# design.net
KiCad netlist of a schematic drawn in Altium Designer
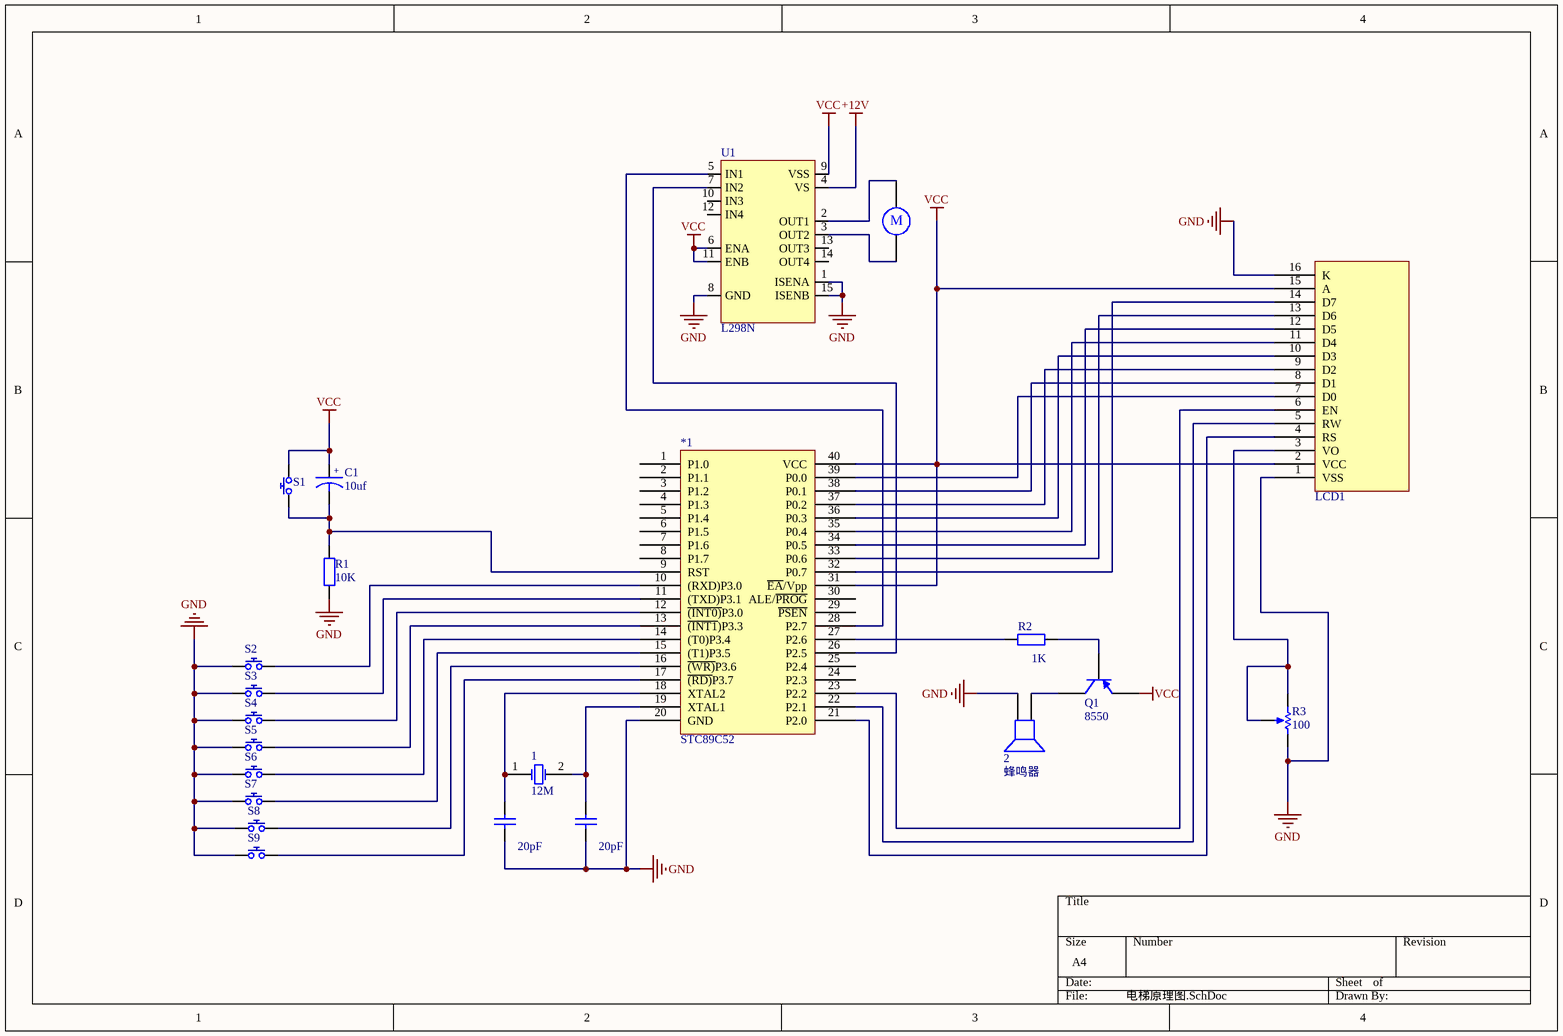
[diagram p0: 电梯原理图.SchDoc]

(export (version "E")
  (design (tool "Eeschema 10.0.6"))
  (components
    (comp (ref "*1") (value "STC89C52") (libsource (lib "AT89C52") (part "Component_1")))
    (comp (ref "1")
      (value "12M")
      (footprint "BCY-W2/D3.1")
      (description "Crystal Oscillator")
      (fields (field (name "PUBLISHER") "Altium Limited"))
      (libsource (lib "Miscellaneous Devices") (part "XTAL"))
    )
    (comp (ref "2")
      (value "蜂鸣器")
      (footprint "PIN2")
      (description "Loudspeaker")
      (fields (field (name "PUBLISHER") "Altium Limited"))
      (libsource (lib "Miscellaneous Devices") (part "Speaker"))
    )
    (comp (ref "B1")
      (value "Motor")
      (footprint "RB5-10.5")
      (description "Motor, General Kind")
      (fields (field (name "PUBLISHER") "Altium Limited"))
      (libsource (lib "Miscellaneous Devices") (part "Motor"))
    )
    (comp (ref "C1")
      (value "10uf")
      (footprint "RB.3/.6")
      (description "电解电容")
      (libsource (lib "MINE") (part "CAP-T"))
    )
    (comp (ref "C2")
      (value "20pF")
      (footprint "RAD-0.3")
      (description "Capacitor")
      (fields (field (name "Comment") "Cap") (field (name "PUBLISHER") "Altium Limited"))
      (libsource (lib "Miscellaneous Devices") (part "Cap"))
    )
    (comp (ref "C3")
      (value "20pF")
      (footprint "RAD-0.3")
      (description "Capacitor")
      (fields (field (name "Comment") "Cap") (field (name "PUBLISHER") "Altium Limited"))
      (libsource (lib "Miscellaneous Devices") (part "Cap"))
    )
    (comp (ref "LCD1") (value "Component_1") (libsource (lib "LCD1602") (part "Component_1")))
    (comp (ref "Q1")
      (value "8550")
      (footprint "SOT-23B_N")
      (description "PNP Bipolar Transistor")
      (fields (field (name "PUBLISHER") "Altium Limited"))
      (libsource (lib "Miscellaneous Devices") (part "PNP"))
    )
    (comp (ref "R1")
      (value "10K")
      (footprint "R-AXIAL0.4")
      (description "插件电阻")
      (libsource (lib "MINE") (part "RES"))
    )
    (comp (ref "R2")
      (value "1K")
      (footprint "AXIAL-0.4")
      (description "Resistor")
      (fields (field (name "Comment") "Res2") (field (name "PUBLISHER") "Altium Limited"))
      (libsource (lib "Miscellaneous Devices") (part "Res2"))
    )
    (comp (ref "R3")
      (value "100")
      (footprint "VR5")
      (description "Potentiometer")
      (fields (field (name "Comment") "RPot") (field (name "PUBLISHER") "Altium Limited"))
      (libsource (lib "Miscellaneous Devices") (part "RPot"))
    )
    (comp (ref "S1")
      (value "~")
      (footprint "KEY_4PIN")
      (description "按键开关")
      (libsource (lib "MINE") (part "Key"))
    )
    (comp (ref "S2")
      (value "~")
      (footprint "KEY_4PIN")
      (description "按键开关")
      (libsource (lib "MINE") (part "Key"))
    )
    (comp (ref "S3")
      (value "~")
      (footprint "KEY_4PIN")
      (description "按键开关")
      (libsource (lib "MINE") (part "Key"))
    )
    (comp (ref "S4")
      (value "~")
      (footprint "KEY_4PIN")
      (description "按键开关")
      (libsource (lib "MINE") (part "Key"))
    )
    (comp (ref "S5")
      (value "~")
      (footprint "KEY_4PIN")
      (description "按键开关")
      (libsource (lib "MINE") (part "Key"))
    )
    (comp (ref "S6")
      (value "~")
      (footprint "KEY_4PIN")
      (description "按键开关")
      (libsource (lib "MINE") (part "Key"))
    )
    (comp (ref "S7")
      (value "~")
      (footprint "KEY_4PIN")
      (description "按键开关")
      (libsource (lib "MINE") (part "Key"))
    )
    (comp (ref "S8")
      (value "~")
      (footprint "KEY_4PIN")
      (description "按键开关")
      (libsource (lib "MINE") (part "Key"))
    )
    (comp (ref "S9")
      (value "~")
      (footprint "KEY_4PIN")
      (description "按键开关")
      (libsource (lib "MINE") (part "Key"))
    )
    (comp (ref "U1") (value "L298N") (footprint "L298N") (libsource (lib "IC芯片") (part "L298N")))
  )
  (nets
    (net (code "1") (name "+12V") (class "Default")
      (node (ref "U1") (pin "4") (pinfunction "VS_4") (pintype "passive"))
    )
    (net (code "2") (name "GND") (class "Default")
      (node (ref "*1") (pin "20") (pinfunction "GND_20") (pintype "passive"))
      (node (ref "2") (pin "2") (pinfunction "2_2") (pintype "passive"))
      (node (ref "C2") (pin "1") (pinfunction "1_1") (pintype "passive"))
      (node (ref "C3") (pin "1") (pinfunction "1_1") (pintype "passive"))
      (node (ref "LCD1") (pin "1") (pinfunction "VSS_1") (pintype "passive"))
      (node (ref "LCD1") (pin "16") (pinfunction "K_16") (pintype "passive"))
      (node (ref "R1") (pin "1") (pinfunction "1_1") (pintype "passive"))
      (node (ref "R3") (pin "2") (pinfunction "BOT_2") (pintype "passive"))
      (node (ref "S2") (pin "1") (pinfunction "1_1") (pintype "passive"))
      (node (ref "S3") (pin "1") (pinfunction "1_1") (pintype "passive"))
      (node (ref "S4") (pin "1") (pinfunction "1_1") (pintype "passive"))
      (node (ref "S5") (pin "1") (pinfunction "1_1") (pintype "passive"))
      (node (ref "S6") (pin "1") (pinfunction "1_1") (pintype "passive"))
      (node (ref "S7") (pin "1") (pinfunction "1_1") (pintype "passive"))
      (node (ref "S8") (pin "1") (pinfunction "1_1") (pintype "passive"))
      (node (ref "S9") (pin "1") (pinfunction "1_1") (pintype "passive"))
      (node (ref "U1") (pin "1") (pinfunction "ISENA_1") (pintype "passive"))
      (node (ref "U1") (pin "15") (pinfunction "ISENB_15") (pintype "passive"))
      (node (ref "U1") (pin "8") (pinfunction "GND_8") (pintype "passive"))
    )
    (net (code "3") (name "Net-(*1-(RXD)P3.0)") (class "Default")
      (node (ref "*1") (pin "10") (pinfunction "(RXD)P3.0_10") (pintype "passive"))
      (node (ref "S2") (pin "2") (pinfunction "2_2") (pintype "passive"))
    )
    (net (code "4") (name "Net-(*1-(T0)P3.4)") (class "Default")
      (node (ref "*1") (pin "14") (pinfunction "(T0)P3.4_14") (pintype "passive"))
      (node (ref "S6") (pin "2") (pinfunction "2_2") (pintype "passive"))
    )
    (net (code "5") (name "Net-(*1-(T1)P3.5)") (class "Default")
      (node (ref "*1") (pin "15") (pinfunction "(T1)P3.5_15") (pintype "passive"))
      (node (ref "S7") (pin "2") (pinfunction "2_2") (pintype "passive"))
    )
    (net (code "6") (name "Net-(*1-(TXD)P3.1)") (class "Default")
      (node (ref "*1") (pin "11") (pinfunction "(TXD)P3.1_11") (pintype "passive"))
      (node (ref "S3") (pin "2") (pinfunction "2_2") (pintype "passive"))
    )
    (net (code "7") (name "Net-(*1-P0.0)") (class "Default")
      (node (ref "*1") (pin "39") (pinfunction "P0.0_39") (pintype "passive"))
      (node (ref "LCD1") (pin "7") (pinfunction "D0_7") (pintype "passive"))
    )
    (net (code "8") (name "Net-(*1-P0.1)") (class "Default")
      (node (ref "*1") (pin "38") (pinfunction "P0.1_38") (pintype "passive"))
      (node (ref "LCD1") (pin "8") (pinfunction "D1_8") (pintype "passive"))
    )
    (net (code "9") (name "Net-(*1-P0.2)") (class "Default")
      (node (ref "*1") (pin "37") (pinfunction "P0.2_37") (pintype "passive"))
      (node (ref "LCD1") (pin "9") (pinfunction "D2_9") (pintype "passive"))
    )
    (net (code "10") (name "Net-(*1-P0.3)") (class "Default")
      (node (ref "*1") (pin "36") (pinfunction "P0.3_36") (pintype "passive"))
      (node (ref "LCD1") (pin "10") (pinfunction "D3_10") (pintype "passive"))
    )
    (net (code "11") (name "Net-(*1-P0.4)") (class "Default")
      (node (ref "*1") (pin "35") (pinfunction "P0.4_35") (pintype "passive"))
      (node (ref "LCD1") (pin "11") (pinfunction "D4_11") (pintype "passive"))
    )
    (net (code "12") (name "Net-(*1-P0.5)") (class "Default")
      (node (ref "*1") (pin "34") (pinfunction "P0.5_34") (pintype "passive"))
      (node (ref "LCD1") (pin "12") (pinfunction "D5_12") (pintype "passive"))
    )
    (net (code "13") (name "Net-(*1-P0.6)") (class "Default")
      (node (ref "*1") (pin "33") (pinfunction "P0.6_33") (pintype "passive"))
      (node (ref "LCD1") (pin "13") (pinfunction "D6_13") (pintype "passive"))
    )
    (net (code "14") (name "Net-(*1-P0.7)") (class "Default")
      (node (ref "*1") (pin "32") (pinfunction "P0.7_32") (pintype "passive"))
      (node (ref "LCD1") (pin "14") (pinfunction "D7_14") (pintype "passive"))
    )
    (net (code "15") (name "Net-(*1-P2.0)") (class "Default")
      (node (ref "*1") (pin "21") (pinfunction "P2.0_21") (pintype "passive"))
      (node (ref "LCD1") (pin "4") (pinfunction "RS_4") (pintype "passive"))
    )
    (net (code "16") (name "Net-(*1-P2.1)") (class "Default")
      (node (ref "*1") (pin "22") (pinfunction "P2.1_22") (pintype "passive"))
      (node (ref "LCD1") (pin "5") (pinfunction "RW_5") (pintype "passive"))
    )
    (net (code "17") (name "Net-(*1-P2.2)") (class "Default")
      (node (ref "*1") (pin "23") (pinfunction "P2.2_23") (pintype "passive"))
      (node (ref "LCD1") (pin "6") (pinfunction "EN_6") (pintype "passive"))
    )
    (net (code "18") (name "Net-(*1-P2.5)") (class "Default")
      (node (ref "*1") (pin "26") (pinfunction "P2.5_26") (pintype "passive"))
      (node (ref "U1") (pin "7") (pinfunction "IN2_7") (pintype "passive"))
    )
    (net (code "19") (name "Net-(*1-P2.6)") (class "Default")
      (node (ref "*1") (pin "27") (pinfunction "P2.6_27") (pintype "passive"))
      (node (ref "R2") (pin "1") (pinfunction "1_1") (pintype "passive"))
    )
    (net (code "20") (name "Net-(*1-P2.7)") (class "Default")
      (node (ref "*1") (pin "28") (pinfunction "P2.7_28") (pintype "passive"))
      (node (ref "U1") (pin "5") (pinfunction "IN1_5") (pintype "passive"))
    )
    (net (code "21") (name "Net-(*1-RST)") (class "Default")
      (node (ref "*1") (pin "9") (pinfunction "RST_9") (pintype "passive"))
      (node (ref "C1") (pin "2") (pinfunction "2_2") (pintype "passive"))
      (node (ref "R1") (pin "2") (pinfunction "2_2") (pintype "passive"))
      (node (ref "S1") (pin "1") (pinfunction "1_1") (pintype "passive"))
    )
    (net (code "22") (name "Net-(*1-XTAL1)") (class "Default")
      (node (ref "*1") (pin "19") (pinfunction "XTAL1_19") (pintype "passive"))
      (node (ref "1") (pin "2") (pinfunction "OSC2_2") (pintype "passive"))
      (node (ref "C3") (pin "2") (pinfunction "2_2") (pintype "passive"))
    )
    (net (code "23") (name "Net-(*1-XTAL2)") (class "Default")
      (node (ref "*1") (pin "18") (pinfunction "XTAL2_18") (pintype "passive"))
      (node (ref "1") (pin "1") (pinfunction "OSC1_1") (pintype "passive"))
      (node (ref "C2") (pin "2") (pinfunction "2_2") (pintype "passive"))
    )
    (net (code "24") (name "Net-(*1-~{(INT0)}P3.0)") (class "Default")
      (node (ref "*1") (pin "12") (pinfunction "~{(INT0)}P3.0_12") (pintype "passive"))
      (node (ref "S4") (pin "2") (pinfunction "2_2") (pintype "passive"))
    )
    (net (code "25") (name "Net-(*1-~{(INT1})P3.3)") (class "Default")
      (node (ref "*1") (pin "13") (pinfunction "~{(INT1})P3.3_13") (pintype "passive"))
      (node (ref "S5") (pin "2") (pinfunction "2_2") (pintype "passive"))
    )
    (net (code "26") (name "Net-(*1-~{(RD)}P3.7)") (class "Default")
      (node (ref "*1") (pin "17") (pinfunction "~{(RD)}P3.7_17") (pintype "passive"))
      (node (ref "S9") (pin "2") (pinfunction "2_2") (pintype "passive"))
    )
    (net (code "27") (name "Net-(*1-~{(WR)}P3.6)") (class "Default")
      (node (ref "*1") (pin "16") (pinfunction "~{(WR)}P3.6_16") (pintype "passive"))
      (node (ref "S8") (pin "2") (pinfunction "2_2") (pintype "passive"))
    )
    (net (code "28") (name "Net-(LCD1-VO)") (class "Default")
      (node (ref "LCD1") (pin "3") (pinfunction "VO_3") (pintype "passive"))
      (node (ref "R3") (pin "1") (pinfunction "TOP_1") (pintype "passive"))
      (node (ref "R3") (pin "3") (pinfunction "TAP_3") (pintype "passive"))
    )
    (net (code "29") (name "Net-(Q1-B)") (class "Default")
      (node (ref "Q1") (pin "2") (pinfunction "B_2") (pintype "passive"))
      (node (ref "R2") (pin "2") (pinfunction "2_2") (pintype "passive"))
    )
    (net (code "30") (name "Net-(Q1-C)") (class "Default")
      (node (ref "2") (pin "1") (pinfunction "1_1") (pintype "passive"))
      (node (ref "Q1") (pin "1") (pinfunction "C_1") (pintype "passive"))
    )
    (net (code "31") (name "Net-(U1-OUT1)") (class "Default")
      (node (ref "B1") (pin "1") (pinfunction "1_1") (pintype "passive"))
      (node (ref "U1") (pin "2") (pinfunction "OUT1_2") (pintype "passive"))
    )
    (net (code "32") (name "Net-(U1-OUT2)") (class "Default")
      (node (ref "B1") (pin "2") (pinfunction "2_2") (pintype "passive"))
      (node (ref "U1") (pin "3") (pinfunction "OUT2_3") (pintype "passive"))
    )
    (net (code "33") (name "VCC") (class "Default")
      (node (ref "*1") (pin "31") (pinfunction "~{EA}/Vpp_31") (pintype "passive"))
      (node (ref "*1") (pin "40") (pinfunction "VCC_40") (pintype "passive"))
      (node (ref "C1") (pin "1") (pinfunction "1_1") (pintype "passive"))
      (node (ref "LCD1") (pin "15") (pinfunction "A_15") (pintype "passive"))
      (node (ref "LCD1") (pin "2") (pinfunction "VCC_2") (pintype "passive"))
      (node (ref "Q1") (pin "3") (pinfunction "E_3") (pintype "passive"))
      (node (ref "S1") (pin "2") (pinfunction "2_2") (pintype "passive"))
      (node (ref "U1") (pin "11") (pinfunction "ENB_11") (pintype "passive"))
      (node (ref "U1") (pin "6") (pinfunction "ENA_6") (pintype "passive"))
      (node (ref "U1") (pin "9") (pinfunction "VSS_9") (pintype "passive"))
    )
    (net (code "34") (name "unconnected-(*1-ALE{slash}~{PROG}-Pad30)") (class "Default")
      (node (ref "*1") (pin "30") (pinfunction "ALE/~{PROG}_30") (pintype "passive"))
    )
    (net (code "35") (name "unconnected-(*1-P1.0-Pad1)") (class "Default")
      (node (ref "*1") (pin "1") (pinfunction "P1.0_1") (pintype "passive"))
    )
    (net (code "36") (name "unconnected-(*1-P1.1-Pad2)") (class "Default")
      (node (ref "*1") (pin "2") (pinfunction "P1.1_2") (pintype "passive"))
    )
    (net (code "37") (name "unconnected-(*1-P1.2-Pad3)") (class "Default")
      (node (ref "*1") (pin "3") (pinfunction "P1.2_3") (pintype "passive"))
    )
    (net (code "38") (name "unconnected-(*1-P1.3-Pad4)") (class "Default")
      (node (ref "*1") (pin "4") (pinfunction "P1.3_4") (pintype "passive"))
    )
    (net (code "39") (name "unconnected-(*1-P1.4-Pad5)") (class "Default")
      (node (ref "*1") (pin "5") (pinfunction "P1.4_5") (pintype "passive"))
    )
    (net (code "40") (name "unconnected-(*1-P1.5-Pad6)") (class "Default")
      (node (ref "*1") (pin "6") (pinfunction "P1.5_6") (pintype "passive"))
    )
    (net (code "41") (name "unconnected-(*1-P1.6-Pad7)") (class "Default")
      (node (ref "*1") (pin "7") (pinfunction "P1.6_7") (pintype "passive"))
    )
    (net (code "42") (name "unconnected-(*1-P1.7-Pad8)") (class "Default")
      (node (ref "*1") (pin "8") (pinfunction "P1.7_8") (pintype "passive"))
    )
    (net (code "43") (name "unconnected-(*1-P2.3-Pad24)") (class "Default")
      (node (ref "*1") (pin "24") (pinfunction "P2.3_24") (pintype "passive"))
    )
    (net (code "44") (name "unconnected-(*1-P2.4-Pad25)") (class "Default")
      (node (ref "*1") (pin "25") (pinfunction "P2.4_25") (pintype "passive"))
    )
    (net (code "45") (name "unconnected-(*1-~{PSEN}-Pad29)") (class "Default")
      (node (ref "*1") (pin "29") (pinfunction "~{PSEN}_29") (pintype "passive"))
    )
    (net (code "46") (name "unconnected-(U1-IN3-Pad10)") (class "Default")
      (node (ref "U1") (pin "10") (pinfunction "IN3_10") (pintype "passive"))
    )
    (net (code "47") (name "unconnected-(U1-IN4-Pad12)") (class "Default")
      (node (ref "U1") (pin "12") (pinfunction "IN4_12") (pintype "passive"))
    )
    (net (code "48") (name "unconnected-(U1-OUT3-Pad13)") (class "Default")
      (node (ref "U1") (pin "13") (pinfunction "OUT3_13") (pintype "passive"))
    )
    (net (code "49") (name "unconnected-(U1-OUT4-Pad14)") (class "Default")
      (node (ref "U1") (pin "14") (pinfunction "OUT4_14") (pintype "passive"))
    )
  )
)
